# 03_MotorStage_v1.net
KiCad netlist of a schematic drawn in EAGLE
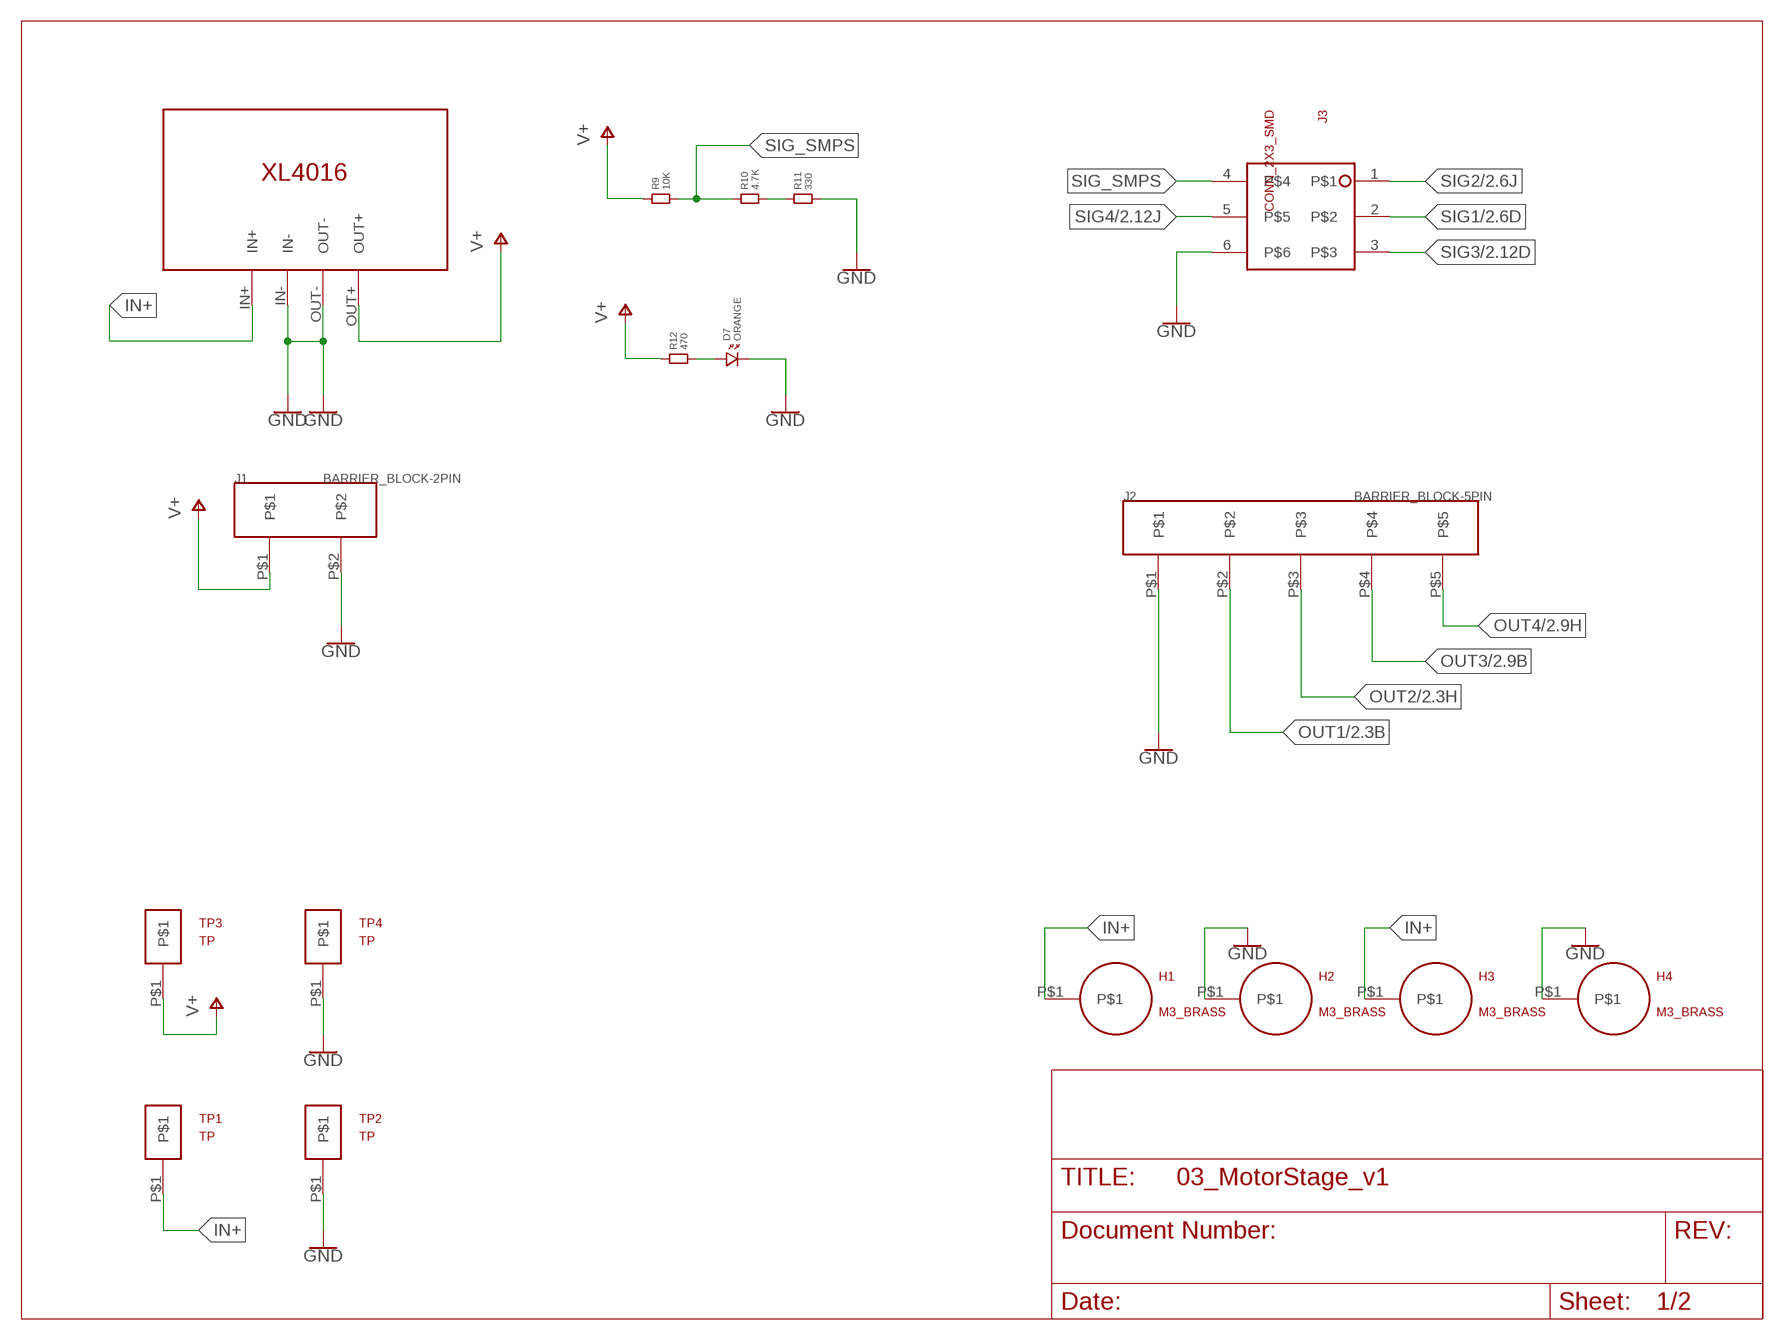
[diagram p0: schematic, sheet 1]
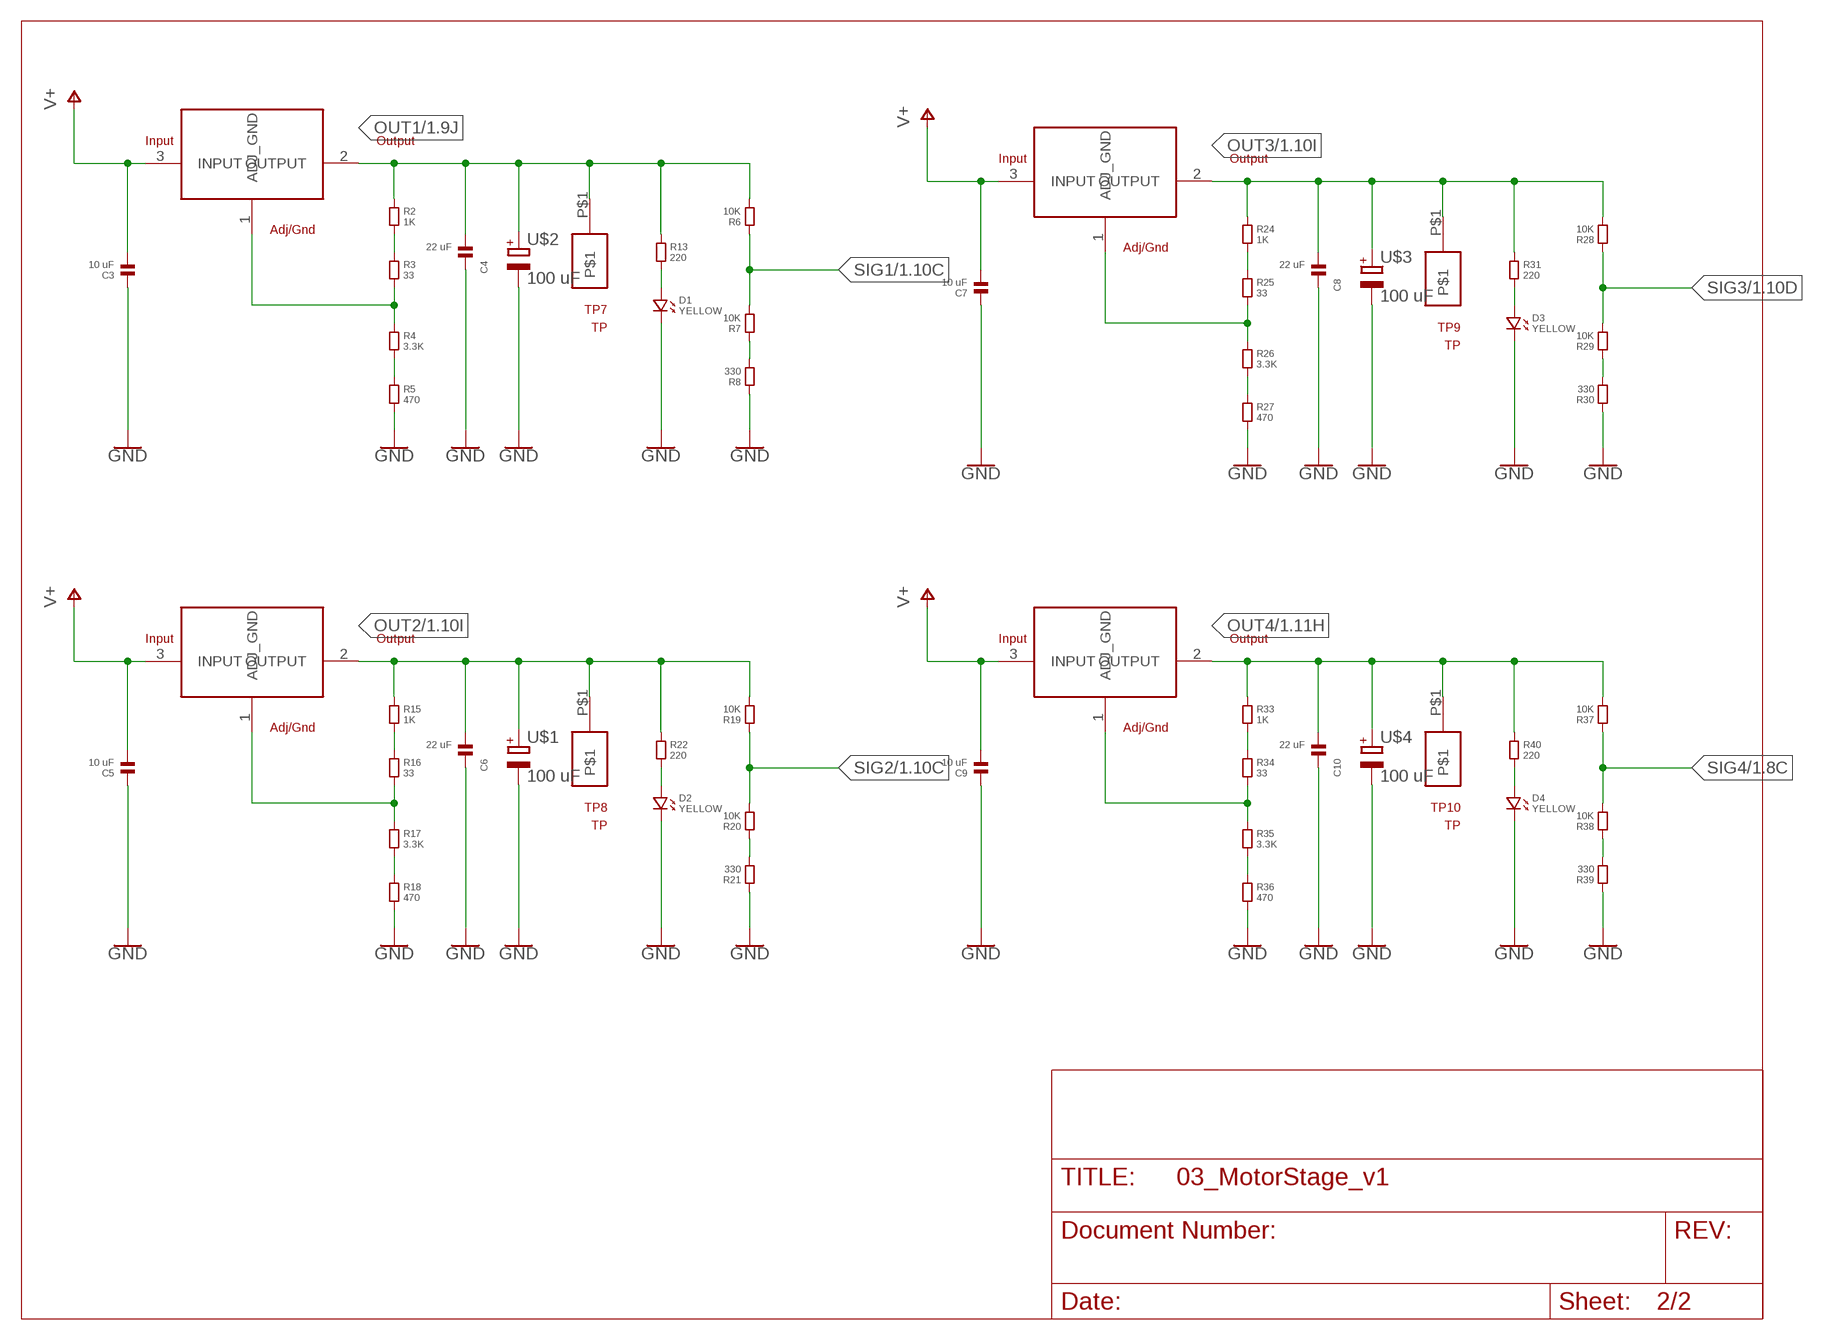
[diagram p1: schematic, sheet 2]

(export (version "E")
  (design (tool "Eeschema 10.0.6"))
  (components
    (comp (ref "C3")
      (value "10 uF")
      (footprint "eagle-import:1206")
      (libsource (lib "eagle-import") (part "CAPACITOR.1206"))
    )
    (comp (ref "C4")
      (value "22 uF")
      (footprint "eagle-import:1206")
      (libsource (lib "eagle-import") (part "CAPACITOR.1206"))
    )
    (comp (ref "C5")
      (value "10 uF")
      (footprint "eagle-import:1206")
      (libsource (lib "eagle-import") (part "CAPACITOR.1206"))
    )
    (comp (ref "C6")
      (value "22 uF")
      (footprint "eagle-import:1206")
      (libsource (lib "eagle-import") (part "CAPACITOR.1206"))
    )
    (comp (ref "C7")
      (value "10 uF")
      (footprint "eagle-import:1206")
      (libsource (lib "eagle-import") (part "CAPACITOR.1206"))
    )
    (comp (ref "C8")
      (value "22 uF")
      (footprint "eagle-import:1206")
      (libsource (lib "eagle-import") (part "CAPACITOR.1206"))
    )
    (comp (ref "C9")
      (value "10 uF")
      (footprint "eagle-import:1206")
      (libsource (lib "eagle-import") (part "CAPACITOR.1206"))
    )
    (comp (ref "C10")
      (value "22 uF")
      (footprint "eagle-import:1206")
      (libsource (lib "eagle-import") (part "CAPACITOR.1206"))
    )
    (comp (ref "D1")
      (value "YELLOW")
      (footprint "eagle-import:1206.LED")
      (libsource (lib "eagle-import") (part "LED.1206"))
    )
    (comp (ref "D2")
      (value "YELLOW")
      (footprint "eagle-import:1206.LED")
      (libsource (lib "eagle-import") (part "LED.1206"))
    )
    (comp (ref "D3")
      (value "YELLOW")
      (footprint "eagle-import:1206.LED")
      (libsource (lib "eagle-import") (part "LED.1206"))
    )
    (comp (ref "D4")
      (value "YELLOW")
      (footprint "eagle-import:1206.LED")
      (libsource (lib "eagle-import") (part "LED.1206"))
    )
    (comp (ref "R1")
      (value "AZ1084C")
      (footprint "eagle-import:AZ1084C")
      (libsource (lib "eagle-import") (part "AZ1084C"))
    )
    (comp (ref "R2")
      (value "1K")
      (footprint "eagle-import:1206")
      (libsource (lib "eagle-import") (part "RESISTOR.1206"))
    )
    (comp (ref "R3")
      (value "33")
      (footprint "eagle-import:1206")
      (libsource (lib "eagle-import") (part "RESISTOR.1206"))
    )
    (comp (ref "R4")
      (value "3.3K")
      (footprint "eagle-import:1206")
      (libsource (lib "eagle-import") (part "RESISTOR.1206"))
    )
    (comp (ref "R5")
      (value "470")
      (footprint "eagle-import:1206")
      (libsource (lib "eagle-import") (part "RESISTOR.1206"))
    )
    (comp (ref "R6")
      (value "10K")
      (footprint "eagle-import:1206")
      (libsource (lib "eagle-import") (part "RESISTOR.1206"))
    )
    (comp (ref "R7")
      (value "10K")
      (footprint "eagle-import:1206")
      (libsource (lib "eagle-import") (part "RESISTOR.1206"))
    )
    (comp (ref "R8")
      (value "330")
      (footprint "eagle-import:1206")
      (libsource (lib "eagle-import") (part "RESISTOR.1206"))
    )
    (comp (ref "R13")
      (value "220")
      (footprint "eagle-import:1206")
      (libsource (lib "eagle-import") (part "RESISTOR.1206"))
    )
    (comp (ref "R14")
      (value "AZ1084C")
      (footprint "eagle-import:AZ1084C")
      (libsource (lib "eagle-import") (part "AZ1084C"))
    )
    (comp (ref "R15")
      (value "1K")
      (footprint "eagle-import:1206")
      (libsource (lib "eagle-import") (part "RESISTOR.1206"))
    )
    (comp (ref "R16")
      (value "33")
      (footprint "eagle-import:1206")
      (libsource (lib "eagle-import") (part "RESISTOR.1206"))
    )
    (comp (ref "R17")
      (value "3.3K")
      (footprint "eagle-import:1206")
      (libsource (lib "eagle-import") (part "RESISTOR.1206"))
    )
    (comp (ref "R18")
      (value "470")
      (footprint "eagle-import:1206")
      (libsource (lib "eagle-import") (part "RESISTOR.1206"))
    )
    (comp (ref "R19")
      (value "10K")
      (footprint "eagle-import:1206")
      (libsource (lib "eagle-import") (part "RESISTOR.1206"))
    )
    (comp (ref "R20")
      (value "10K")
      (footprint "eagle-import:1206")
      (libsource (lib "eagle-import") (part "RESISTOR.1206"))
    )
    (comp (ref "R21")
      (value "330")
      (footprint "eagle-import:1206")
      (libsource (lib "eagle-import") (part "RESISTOR.1206"))
    )
    (comp (ref "R22")
      (value "220")
      (footprint "eagle-import:1206")
      (libsource (lib "eagle-import") (part "RESISTOR.1206"))
    )
    (comp (ref "R23")
      (value "AZ1084C")
      (footprint "eagle-import:AZ1084C")
      (libsource (lib "eagle-import") (part "AZ1084C"))
    )
    (comp (ref "R24")
      (value "1K")
      (footprint "eagle-import:1206")
      (libsource (lib "eagle-import") (part "RESISTOR.1206"))
    )
    (comp (ref "R25")
      (value "33")
      (footprint "eagle-import:1206")
      (libsource (lib "eagle-import") (part "RESISTOR.1206"))
    )
    (comp (ref "R26")
      (value "3.3K")
      (footprint "eagle-import:1206")
      (libsource (lib "eagle-import") (part "RESISTOR.1206"))
    )
    (comp (ref "R27")
      (value "470")
      (footprint "eagle-import:1206")
      (libsource (lib "eagle-import") (part "RESISTOR.1206"))
    )
    (comp (ref "R28")
      (value "10K")
      (footprint "eagle-import:1206")
      (libsource (lib "eagle-import") (part "RESISTOR.1206"))
    )
    (comp (ref "R29")
      (value "10K")
      (footprint "eagle-import:1206")
      (libsource (lib "eagle-import") (part "RESISTOR.1206"))
    )
    (comp (ref "R30")
      (value "330")
      (footprint "eagle-import:1206")
      (libsource (lib "eagle-import") (part "RESISTOR.1206"))
    )
    (comp (ref "R31")
      (value "220")
      (footprint "eagle-import:1206")
      (libsource (lib "eagle-import") (part "RESISTOR.1206"))
    )
    (comp (ref "R32")
      (value "AZ1084C")
      (footprint "eagle-import:AZ1084C")
      (libsource (lib "eagle-import") (part "AZ1084C"))
    )
    (comp (ref "R33")
      (value "1K")
      (footprint "eagle-import:1206")
      (libsource (lib "eagle-import") (part "RESISTOR.1206"))
    )
    (comp (ref "R34")
      (value "33")
      (footprint "eagle-import:1206")
      (libsource (lib "eagle-import") (part "RESISTOR.1206"))
    )
    (comp (ref "R35")
      (value "3.3K")
      (footprint "eagle-import:1206")
      (libsource (lib "eagle-import") (part "RESISTOR.1206"))
    )
    (comp (ref "R36")
      (value "470")
      (footprint "eagle-import:1206")
      (libsource (lib "eagle-import") (part "RESISTOR.1206"))
    )
    (comp (ref "R37")
      (value "10K")
      (footprint "eagle-import:1206")
      (libsource (lib "eagle-import") (part "RESISTOR.1206"))
    )
    (comp (ref "R38")
      (value "10K")
      (footprint "eagle-import:1206")
      (libsource (lib "eagle-import") (part "RESISTOR.1206"))
    )
    (comp (ref "R39")
      (value "330")
      (footprint "eagle-import:1206")
      (libsource (lib "eagle-import") (part "RESISTOR.1206"))
    )
    (comp (ref "R40")
      (value "220")
      (footprint "eagle-import:1206")
      (libsource (lib "eagle-import") (part "RESISTOR.1206"))
    )
    (comp (ref "TP7") (value "TP") (footprint "eagle-import:TP") (libsource (lib "eagle-import") (part "TP")))
    (comp (ref "TP8") (value "TP") (footprint "eagle-import:TP") (libsource (lib "eagle-import") (part "TP")))
    (comp (ref "TP9") (value "TP") (footprint "eagle-import:TP") (libsource (lib "eagle-import") (part "TP")))
    (comp (ref "TP10")
      (value "TP")
      (footprint "eagle-import:TP")
      (libsource (lib "eagle-import") (part "TP"))
    )
    (comp (ref "U$1")
      (value "100 uF")
      (footprint "eagle-import:ELECTROLYTIC_CAP")
      (fields (field (name "MF") "Wurth Electronics") (field (name "MP") "865080545012"))
      (libsource (lib "eagle-import") (part "ELECTROLYTIC_CAP"))
    )
    (comp (ref "U$2")
      (value "100 uF")
      (footprint "eagle-import:ELECTROLYTIC_CAP")
      (fields (field (name "MF") "Wurth Electronics") (field (name "MP") "865080545012"))
      (libsource (lib "eagle-import") (part "ELECTROLYTIC_CAP"))
    )
    (comp (ref "U$3")
      (value "100 uF")
      (footprint "eagle-import:ELECTROLYTIC_CAP")
      (fields (field (name "MF") "Wurth Electronics") (field (name "MP") "865080545012"))
      (libsource (lib "eagle-import") (part "ELECTROLYTIC_CAP"))
    )
    (comp (ref "U$4")
      (value "100 uF")
      (footprint "eagle-import:ELECTROLYTIC_CAP")
      (fields (field (name "MF") "Wurth Electronics") (field (name "MP") "865080545012"))
      (libsource (lib "eagle-import") (part "ELECTROLYTIC_CAP"))
    )
    (comp (ref "D7")
      (value "ORANGE")
      (footprint "eagle-import:1206.LED")
      (libsource (lib "eagle-import") (part "LED.1206"))
    )
    (comp (ref "H1")
      (value "M3_BRASS")
      (footprint "eagle-import:M3_BRASS")
      (libsource (lib "eagle-import") (part "M3_BRASS"))
    )
    (comp (ref "H2")
      (value "M3_BRASS")
      (footprint "eagle-import:M3_BRASS")
      (libsource (lib "eagle-import") (part "M3_BRASS"))
    )
    (comp (ref "H3")
      (value "M3_BRASS")
      (footprint "eagle-import:M3_BRASS")
      (libsource (lib "eagle-import") (part "M3_BRASS"))
    )
    (comp (ref "H4")
      (value "M3_BRASS")
      (footprint "eagle-import:M3_BRASS")
      (libsource (lib "eagle-import") (part "M3_BRASS"))
    )
    (comp (ref "J1")
      (value "BARRIER_BLOCK-2PIN")
      (footprint "eagle-import:BARRIERBLOCK-2PIN")
      (libsource (lib "eagle-import") (part "BARRIER_BLOCK-2PIN"))
    )
    (comp (ref "J2")
      (value "BARRIER_BLOCK-5PIN")
      (footprint "eagle-import:BARRIERBLOCK-5PIN")
      (libsource (lib "eagle-import") (part "BARRIER_BLOCK-5PIN"))
    )
    (comp (ref "J3")
      (value "CONN_2X3_SMD")
      (footprint "eagle-import:2X3_SMD_CONNECTOR")
      (libsource (lib "eagle-import") (part "CONN_2X3_SMD"))
    )
    (comp (ref "R9")
      (value "10K")
      (footprint "eagle-import:1206")
      (libsource (lib "eagle-import") (part "RESISTOR.1206"))
    )
    (comp (ref "R10")
      (value "4.7K")
      (footprint "eagle-import:1206")
      (libsource (lib "eagle-import") (part "RESISTOR.1206"))
    )
    (comp (ref "R11")
      (value "330")
      (footprint "eagle-import:1206")
      (libsource (lib "eagle-import") (part "RESISTOR.1206"))
    )
    (comp (ref "R12")
      (value "470")
      (footprint "eagle-import:1206")
      (libsource (lib "eagle-import") (part "RESISTOR.1206"))
    )
    (comp (ref "TP1") (value "TP") (footprint "eagle-import:TP") (libsource (lib "eagle-import") (part "TP")))
    (comp (ref "TP2") (value "TP") (footprint "eagle-import:TP") (libsource (lib "eagle-import") (part "TP")))
    (comp (ref "TP3") (value "TP") (footprint "eagle-import:TP") (libsource (lib "eagle-import") (part "TP")))
    (comp (ref "TP4") (value "TP") (footprint "eagle-import:TP") (libsource (lib "eagle-import") (part "TP")))
    (comp (ref "U1")
      (value "XL4016-DEV")
      (footprint "eagle-import:XL4016-DEV")
      (libsource (lib "eagle-import") (part "XL4016-DEV"))
    )
  )
  (nets
    (net (code "1") (name "GND") (class "Default")
      (node (ref "C10") (pin "1") (pinfunction "1_1") (pintype "bidirectional"))
      (node (ref "C3") (pin "1") (pinfunction "1_1") (pintype "bidirectional"))
      (node (ref "C4") (pin "1") (pinfunction "1_1") (pintype "bidirectional"))
      (node (ref "C5") (pin "1") (pinfunction "1_1") (pintype "bidirectional"))
      (node (ref "C6") (pin "1") (pinfunction "1_1") (pintype "bidirectional"))
      (node (ref "C7") (pin "1") (pinfunction "1_1") (pintype "bidirectional"))
      (node (ref "C8") (pin "1") (pinfunction "1_1") (pintype "bidirectional"))
      (node (ref "C9") (pin "1") (pinfunction "1_1") (pintype "bidirectional"))
      (node (ref "D1") (pin "P$2") (pinfunction "2_P$2") (pintype "bidirectional"))
      (node (ref "D2") (pin "P$2") (pinfunction "2_P$2") (pintype "bidirectional"))
      (node (ref "D3") (pin "P$2") (pinfunction "2_P$2") (pintype "bidirectional"))
      (node (ref "D4") (pin "P$2") (pinfunction "2_P$2") (pintype "bidirectional"))
      (node (ref "D7") (pin "P$2") (pinfunction "2_P$2") (pintype "bidirectional"))
      (node (ref "H2") (pin "P$1") (pinfunction "P$1_P$1") (pintype "bidirectional"))
      (node (ref "H4") (pin "P$1") (pinfunction "P$1_P$1") (pintype "bidirectional"))
      (node (ref "J1") (pin "P$2") (pinfunction "P$2_P$2") (pintype "bidirectional"))
      (node (ref "J2") (pin "P$1") (pinfunction "P$1_P$1") (pintype "bidirectional"))
      (node (ref "J3") (pin "6") (pinfunction "P$6_6") (pintype "bidirectional"))
      (node (ref "R11") (pin "2") (pinfunction "2_2") (pintype "bidirectional"))
      (node (ref "R18") (pin "2") (pinfunction "2_2") (pintype "bidirectional"))
      (node (ref "R21") (pin "1") (pinfunction "1_1") (pintype "bidirectional"))
      (node (ref "R27") (pin "2") (pinfunction "2_2") (pintype "bidirectional"))
      (node (ref "R30") (pin "1") (pinfunction "1_1") (pintype "bidirectional"))
      (node (ref "R36") (pin "2") (pinfunction "2_2") (pintype "bidirectional"))
      (node (ref "R39") (pin "1") (pinfunction "1_1") (pintype "bidirectional"))
      (node (ref "R5") (pin "2") (pinfunction "2_2") (pintype "bidirectional"))
      (node (ref "R8") (pin "1") (pinfunction "1_1") (pintype "bidirectional"))
      (node (ref "TP2") (pin "P$1") (pinfunction "P$1_P$1") (pintype "bidirectional"))
      (node (ref "TP4") (pin "P$1") (pinfunction "P$1_P$1") (pintype "bidirectional"))
      (node (ref "U$1") (pin "-") (pinfunction "-_-") (pintype "passive"))
      (node (ref "U$2") (pin "-") (pinfunction "-_-") (pintype "passive"))
      (node (ref "U$3") (pin "-") (pinfunction "-_-") (pintype "passive"))
      (node (ref "U$4") (pin "-") (pinfunction "-_-") (pintype "passive"))
      (node (ref "U1") (pin "IN-") (pinfunction "IN-_IN-") (pintype "bidirectional"))
      (node (ref "U1") (pin "OUT-") (pinfunction "OUT-_OUT-") (pintype "bidirectional"))
    )
    (net (code "2") (name "IN+") (class "Default")
      (node (ref "H1") (pin "P$1") (pinfunction "P$1_P$1") (pintype "bidirectional"))
      (node (ref "H3") (pin "P$1") (pinfunction "P$1_P$1") (pintype "bidirectional"))
      (node (ref "TP1") (pin "P$1") (pinfunction "P$1_P$1") (pintype "bidirectional"))
      (node (ref "U1") (pin "IN+") (pinfunction "IN+_IN+") (pintype "bidirectional"))
    )
    (net (code "3") (name "Net-(D1-1)") (class "Default")
      (node (ref "D1") (pin "P$1") (pinfunction "1_P$1") (pintype "bidirectional"))
      (node (ref "R13") (pin "2") (pinfunction "2_2") (pintype "bidirectional"))
    )
    (net (code "4") (name "Net-(D2-1)") (class "Default")
      (node (ref "D2") (pin "P$1") (pinfunction "1_P$1") (pintype "bidirectional"))
      (node (ref "R22") (pin "2") (pinfunction "2_2") (pintype "bidirectional"))
    )
    (net (code "5") (name "Net-(D3-1)") (class "Default")
      (node (ref "D3") (pin "P$1") (pinfunction "1_P$1") (pintype "bidirectional"))
      (node (ref "R31") (pin "2") (pinfunction "2_2") (pintype "bidirectional"))
    )
    (net (code "6") (name "Net-(D4-1)") (class "Default")
      (node (ref "D4") (pin "P$1") (pinfunction "1_P$1") (pintype "bidirectional"))
      (node (ref "R40") (pin "2") (pinfunction "2_2") (pintype "bidirectional"))
    )
    (net (code "7") (name "Net-(D7-1)") (class "Default")
      (node (ref "D7") (pin "P$1") (pinfunction "1_P$1") (pintype "bidirectional"))
      (node (ref "R12") (pin "2") (pinfunction "2_2") (pintype "bidirectional"))
    )
    (net (code "8") (name "Net-(R1-ADJ_GND)") (class "Default")
      (node (ref "R1") (pin "1") (pinfunction "ADJ_GND_1") (pintype "bidirectional"))
      (node (ref "R3") (pin "2") (pinfunction "2_2") (pintype "bidirectional"))
      (node (ref "R4") (pin "1") (pinfunction "1_1") (pintype "bidirectional"))
    )
    (net (code "9") (name "Net-(R2-Pad2)") (class "Default")
      (node (ref "R2") (pin "2") (pinfunction "2_2") (pintype "bidirectional"))
      (node (ref "R3") (pin "1") (pinfunction "1_1") (pintype "bidirectional"))
    )
    (net (code "10") (name "Net-(R4-Pad2)") (class "Default")
      (node (ref "R4") (pin "2") (pinfunction "2_2") (pintype "bidirectional"))
      (node (ref "R5") (pin "1") (pinfunction "1_1") (pintype "bidirectional"))
    )
    (net (code "11") (name "Net-(R7-Pad1)") (class "Default")
      (node (ref "R7") (pin "1") (pinfunction "1_1") (pintype "bidirectional"))
      (node (ref "R8") (pin "2") (pinfunction "2_2") (pintype "bidirectional"))
    )
    (net (code "12") (name "Net-(R10-Pad2)") (class "Default")
      (node (ref "R10") (pin "2") (pinfunction "2_2") (pintype "bidirectional"))
      (node (ref "R11") (pin "1") (pinfunction "1_1") (pintype "bidirectional"))
    )
    (net (code "13") (name "Net-(R14-ADJ_GND)") (class "Default")
      (node (ref "R14") (pin "1") (pinfunction "ADJ_GND_1") (pintype "bidirectional"))
      (node (ref "R16") (pin "2") (pinfunction "2_2") (pintype "bidirectional"))
      (node (ref "R17") (pin "1") (pinfunction "1_1") (pintype "bidirectional"))
    )
    (net (code "14") (name "Net-(R15-Pad2)") (class "Default")
      (node (ref "R15") (pin "2") (pinfunction "2_2") (pintype "bidirectional"))
      (node (ref "R16") (pin "1") (pinfunction "1_1") (pintype "bidirectional"))
    )
    (net (code "15") (name "Net-(R17-Pad2)") (class "Default")
      (node (ref "R17") (pin "2") (pinfunction "2_2") (pintype "bidirectional"))
      (node (ref "R18") (pin "1") (pinfunction "1_1") (pintype "bidirectional"))
    )
    (net (code "16") (name "Net-(R20-Pad1)") (class "Default")
      (node (ref "R20") (pin "1") (pinfunction "1_1") (pintype "bidirectional"))
      (node (ref "R21") (pin "2") (pinfunction "2_2") (pintype "bidirectional"))
    )
    (net (code "17") (name "Net-(R23-ADJ_GND)") (class "Default")
      (node (ref "R23") (pin "1") (pinfunction "ADJ_GND_1") (pintype "bidirectional"))
      (node (ref "R25") (pin "2") (pinfunction "2_2") (pintype "bidirectional"))
      (node (ref "R26") (pin "1") (pinfunction "1_1") (pintype "bidirectional"))
    )
    (net (code "18") (name "Net-(R24-Pad2)") (class "Default")
      (node (ref "R24") (pin "2") (pinfunction "2_2") (pintype "bidirectional"))
      (node (ref "R25") (pin "1") (pinfunction "1_1") (pintype "bidirectional"))
    )
    (net (code "19") (name "Net-(R26-Pad2)") (class "Default")
      (node (ref "R26") (pin "2") (pinfunction "2_2") (pintype "bidirectional"))
      (node (ref "R27") (pin "1") (pinfunction "1_1") (pintype "bidirectional"))
    )
    (net (code "20") (name "Net-(R29-Pad1)") (class "Default")
      (node (ref "R29") (pin "1") (pinfunction "1_1") (pintype "bidirectional"))
      (node (ref "R30") (pin "2") (pinfunction "2_2") (pintype "bidirectional"))
    )
    (net (code "21") (name "Net-(R32-ADJ_GND)") (class "Default")
      (node (ref "R32") (pin "1") (pinfunction "ADJ_GND_1") (pintype "bidirectional"))
      (node (ref "R34") (pin "2") (pinfunction "2_2") (pintype "bidirectional"))
      (node (ref "R35") (pin "1") (pinfunction "1_1") (pintype "bidirectional"))
    )
    (net (code "22") (name "Net-(R33-Pad2)") (class "Default")
      (node (ref "R33") (pin "2") (pinfunction "2_2") (pintype "bidirectional"))
      (node (ref "R34") (pin "1") (pinfunction "1_1") (pintype "bidirectional"))
    )
    (net (code "23") (name "Net-(R35-Pad2)") (class "Default")
      (node (ref "R35") (pin "2") (pinfunction "2_2") (pintype "bidirectional"))
      (node (ref "R36") (pin "1") (pinfunction "1_1") (pintype "bidirectional"))
    )
    (net (code "24") (name "Net-(R38-Pad1)") (class "Default")
      (node (ref "R38") (pin "1") (pinfunction "1_1") (pintype "bidirectional"))
      (node (ref "R39") (pin "2") (pinfunction "2_2") (pintype "bidirectional"))
    )
    (net (code "25") (name "OUT1") (class "Default")
      (node (ref "C4") (pin "2") (pinfunction "2_2") (pintype "bidirectional"))
      (node (ref "J2") (pin "P$2") (pinfunction "P$2_P$2") (pintype "bidirectional"))
      (node (ref "R1") (pin "2") (pinfunction "OUTPUT_2") (pintype "bidirectional"))
      (node (ref "R13") (pin "1") (pinfunction "1_1") (pintype "bidirectional"))
      (node (ref "R2") (pin "1") (pinfunction "1_1") (pintype "bidirectional"))
      (node (ref "R6") (pin "2") (pinfunction "2_2") (pintype "bidirectional"))
      (node (ref "TP7") (pin "P$1") (pinfunction "P$1_P$1") (pintype "bidirectional"))
      (node (ref "U$2") (pin "+") (pinfunction "+_+") (pintype "passive"))
    )
    (net (code "26") (name "OUT2") (class "Default")
      (node (ref "C6") (pin "2") (pinfunction "2_2") (pintype "bidirectional"))
      (node (ref "J2") (pin "P$3") (pinfunction "P$3_P$3") (pintype "bidirectional"))
      (node (ref "R14") (pin "2") (pinfunction "OUTPUT_2") (pintype "bidirectional"))
      (node (ref "R15") (pin "1") (pinfunction "1_1") (pintype "bidirectional"))
      (node (ref "R19") (pin "2") (pinfunction "2_2") (pintype "bidirectional"))
      (node (ref "R22") (pin "1") (pinfunction "1_1") (pintype "bidirectional"))
      (node (ref "TP8") (pin "P$1") (pinfunction "P$1_P$1") (pintype "bidirectional"))
      (node (ref "U$1") (pin "+") (pinfunction "+_+") (pintype "passive"))
    )
    (net (code "27") (name "OUT3") (class "Default")
      (node (ref "C8") (pin "2") (pinfunction "2_2") (pintype "bidirectional"))
      (node (ref "J2") (pin "P$4") (pinfunction "P$4_P$4") (pintype "bidirectional"))
      (node (ref "R23") (pin "2") (pinfunction "OUTPUT_2") (pintype "bidirectional"))
      (node (ref "R24") (pin "1") (pinfunction "1_1") (pintype "bidirectional"))
      (node (ref "R28") (pin "2") (pinfunction "2_2") (pintype "bidirectional"))
      (node (ref "R31") (pin "1") (pinfunction "1_1") (pintype "bidirectional"))
      (node (ref "TP9") (pin "P$1") (pinfunction "P$1_P$1") (pintype "bidirectional"))
      (node (ref "U$3") (pin "+") (pinfunction "+_+") (pintype "passive"))
    )
    (net (code "28") (name "OUT4") (class "Default")
      (node (ref "C10") (pin "2") (pinfunction "2_2") (pintype "bidirectional"))
      (node (ref "J2") (pin "P$5") (pinfunction "P$5_P$5") (pintype "bidirectional"))
      (node (ref "R32") (pin "2") (pinfunction "OUTPUT_2") (pintype "bidirectional"))
      (node (ref "R33") (pin "1") (pinfunction "1_1") (pintype "bidirectional"))
      (node (ref "R37") (pin "2") (pinfunction "2_2") (pintype "bidirectional"))
      (node (ref "R40") (pin "1") (pinfunction "1_1") (pintype "bidirectional"))
      (node (ref "TP10") (pin "P$1") (pinfunction "P$1_P$1") (pintype "bidirectional"))
      (node (ref "U$4") (pin "+") (pinfunction "+_+") (pintype "passive"))
    )
    (net (code "29") (name "SIG1") (class "Default")
      (node (ref "J3") (pin "2") (pinfunction "P$2_2") (pintype "bidirectional"))
      (node (ref "R6") (pin "1") (pinfunction "1_1") (pintype "bidirectional"))
      (node (ref "R7") (pin "2") (pinfunction "2_2") (pintype "bidirectional"))
    )
    (net (code "30") (name "SIG2") (class "Default")
      (node (ref "J3") (pin "1") (pinfunction "P$1_1") (pintype "bidirectional"))
      (node (ref "R19") (pin "1") (pinfunction "1_1") (pintype "bidirectional"))
      (node (ref "R20") (pin "2") (pinfunction "2_2") (pintype "bidirectional"))
    )
    (net (code "31") (name "SIG3") (class "Default")
      (node (ref "J3") (pin "3") (pinfunction "P$3_3") (pintype "bidirectional"))
      (node (ref "R28") (pin "1") (pinfunction "1_1") (pintype "bidirectional"))
      (node (ref "R29") (pin "2") (pinfunction "2_2") (pintype "bidirectional"))
    )
    (net (code "32") (name "SIG4") (class "Default")
      (node (ref "J3") (pin "5") (pinfunction "P$5_5") (pintype "bidirectional"))
      (node (ref "R37") (pin "1") (pinfunction "1_1") (pintype "bidirectional"))
      (node (ref "R38") (pin "2") (pinfunction "2_2") (pintype "bidirectional"))
    )
    (net (code "33") (name "SIG_SMPS") (class "Default")
      (node (ref "J3") (pin "4") (pinfunction "P$4_4") (pintype "bidirectional"))
      (node (ref "R10") (pin "1") (pinfunction "1_1") (pintype "bidirectional"))
      (node (ref "R9") (pin "2") (pinfunction "2_2") (pintype "bidirectional"))
    )
    (net (code "34") (name "V+") (class "Default")
      (node (ref "C3") (pin "2") (pinfunction "2_2") (pintype "bidirectional"))
      (node (ref "C5") (pin "2") (pinfunction "2_2") (pintype "bidirectional"))
      (node (ref "C7") (pin "2") (pinfunction "2_2") (pintype "bidirectional"))
      (node (ref "C9") (pin "2") (pinfunction "2_2") (pintype "bidirectional"))
      (node (ref "J1") (pin "P$1") (pinfunction "P$1_P$1") (pintype "bidirectional"))
      (node (ref "R1") (pin "3") (pinfunction "INPUT_3") (pintype "bidirectional"))
      (node (ref "R12") (pin "1") (pinfunction "1_1") (pintype "bidirectional"))
      (node (ref "R14") (pin "3") (pinfunction "INPUT_3") (pintype "bidirectional"))
      (node (ref "R23") (pin "3") (pinfunction "INPUT_3") (pintype "bidirectional"))
      (node (ref "R32") (pin "3") (pinfunction "INPUT_3") (pintype "bidirectional"))
      (node (ref "R9") (pin "1") (pinfunction "1_1") (pintype "bidirectional"))
      (node (ref "TP3") (pin "P$1") (pinfunction "P$1_P$1") (pintype "bidirectional"))
      (node (ref "U1") (pin "OUT+") (pinfunction "OUT+_OUT+") (pintype "bidirectional"))
    )
  )
)
